# Sheet1.net
KiCad netlist of a schematic drawn in Altium Designer
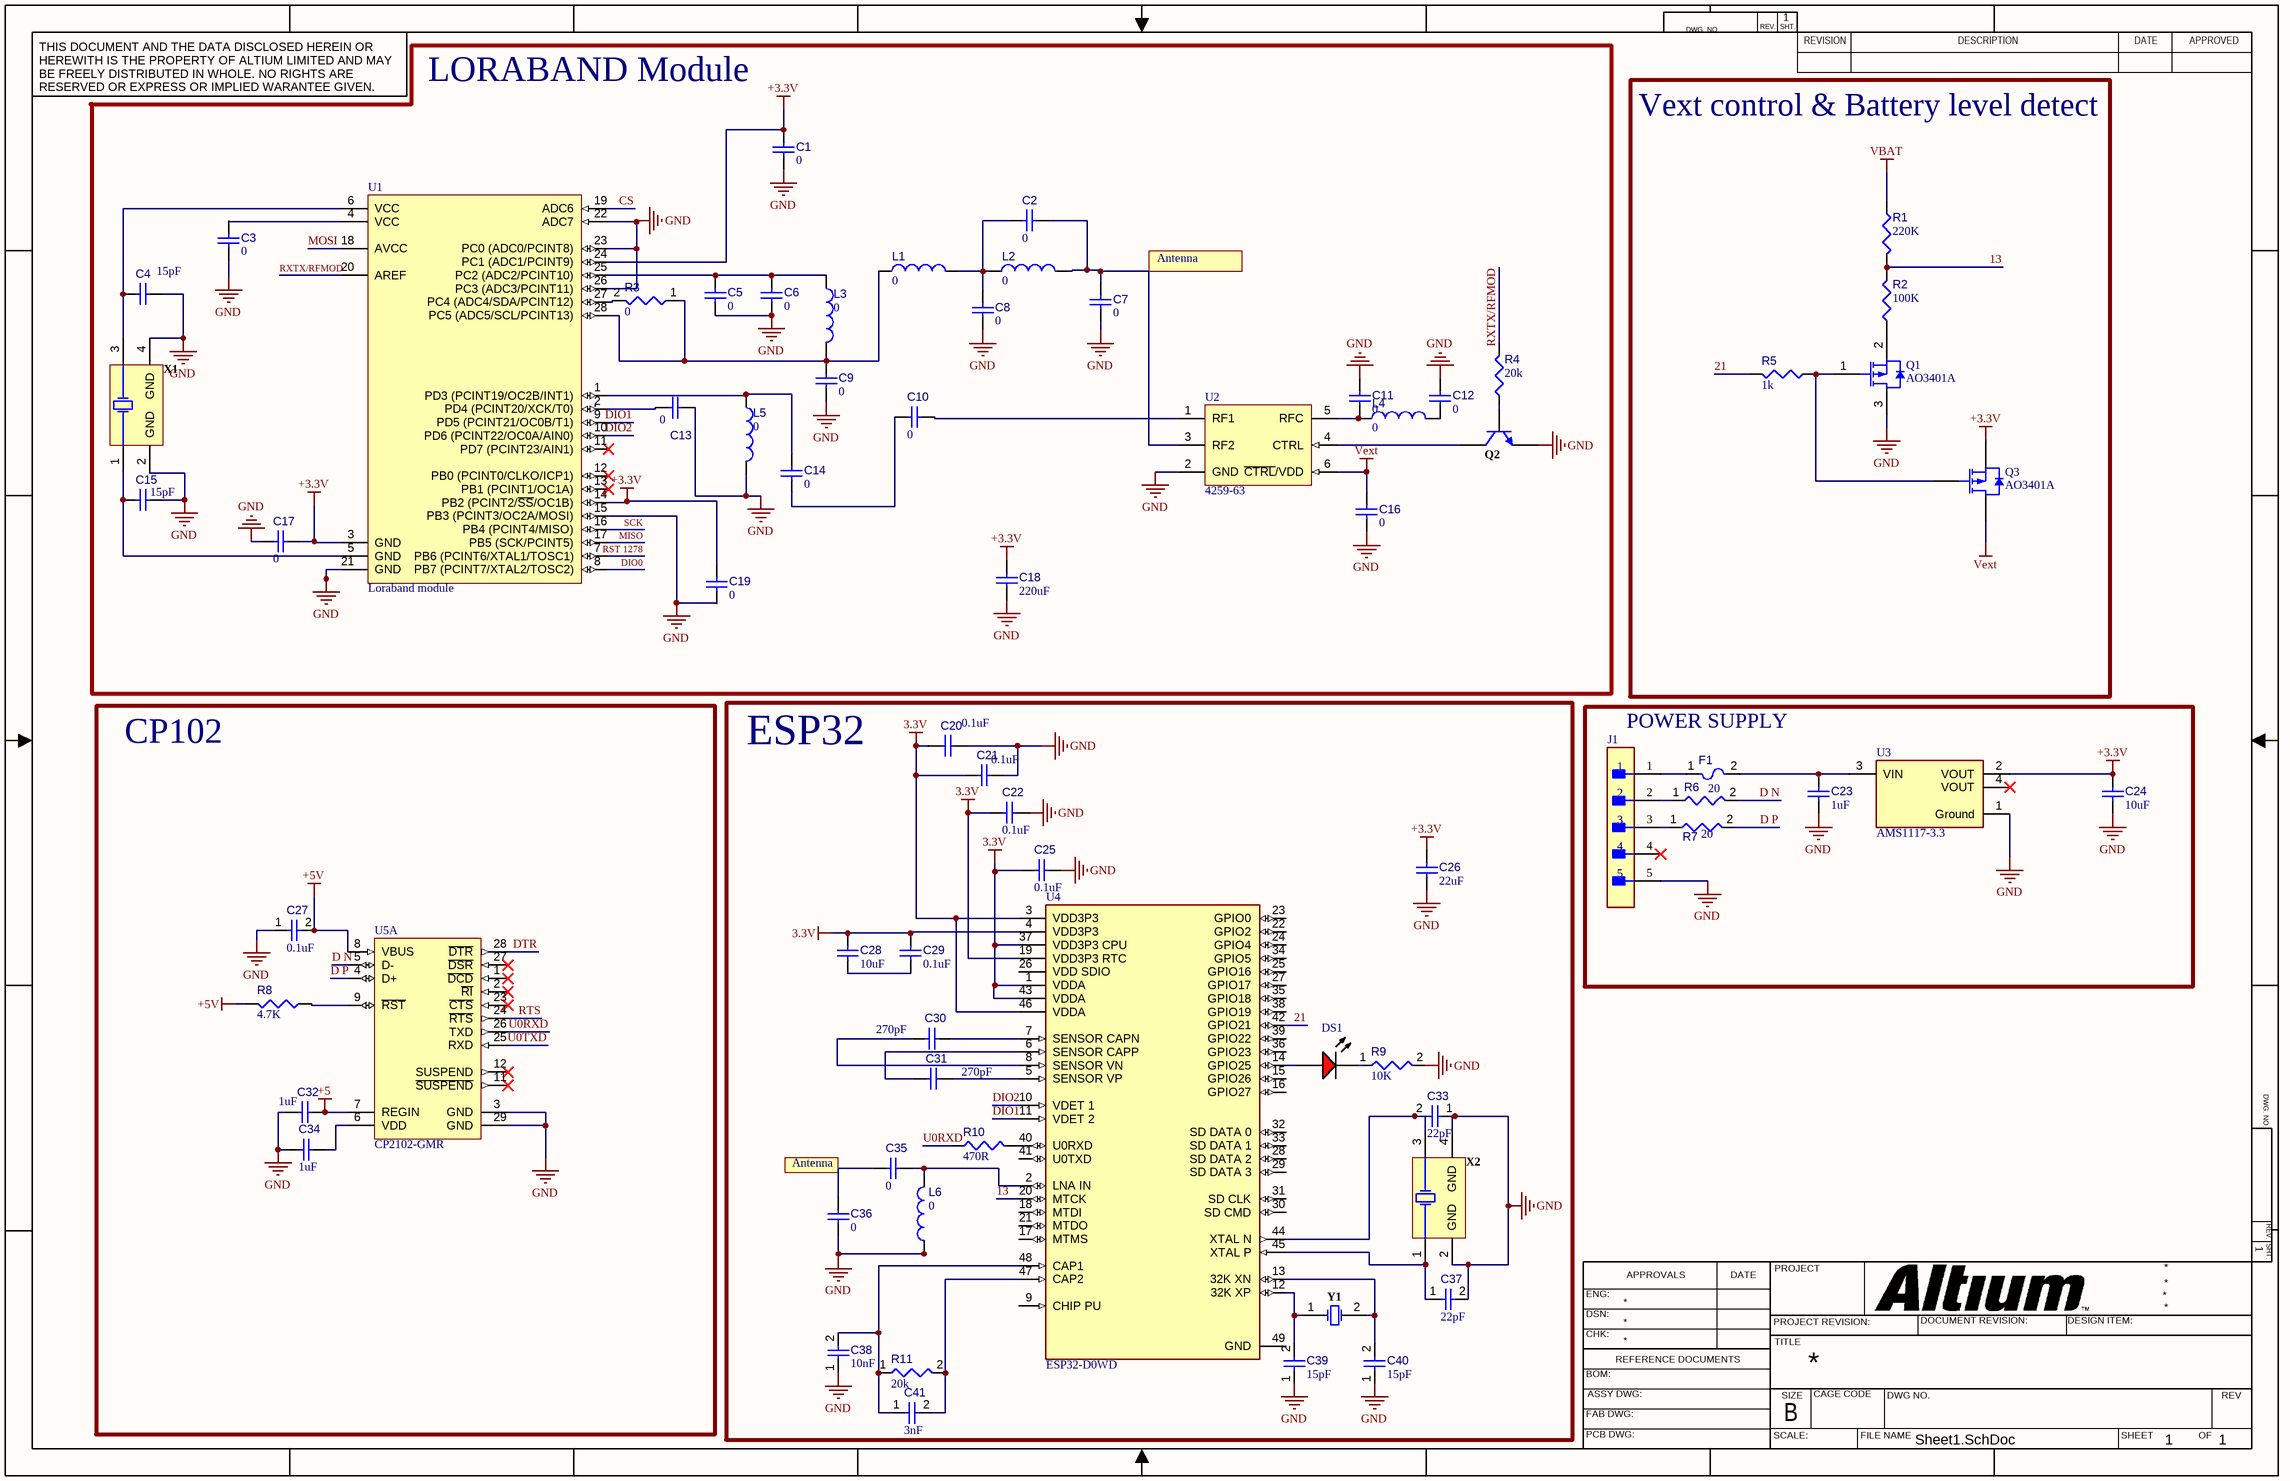
[diagram p0: Sheet1.SchDoc]

(export (version "E")
  (design (tool "Eeschema 10.0.6"))
  (components
    (comp (ref "C1")
      (value "0")
      (footprint "CAPC0402(1005)60_L")
      (description "Chip Capacitor, 10nF +/-20%, 50V, 0402, Thickness 0.6 mm")
      (fields (field (name "TOLERANCE") "5%") (field (name "Comment") "Capacitor 10nF +/-20% 50V 0402"))
      (libsource (lib "University of Moratuwa") (part "CAP-NP-2"))
    )
    (comp (ref "C2")
      (value "0")
      (footprint "CAPC0402(1005)60_L")
      (description "Chip Capacitor, 10nF +/-20%, 50V, 0402, Thickness 0.6 mm")
      (fields (field (name "TOLERANCE") "5%") (field (name "Comment") "Capacitor 10nF +/-20% 50V 0402"))
      (libsource (lib "University of Moratuwa") (part "CAP-NP-2"))
    )
    (comp (ref "C3")
      (value "0")
      (footprint "CAPC0402(1005)60_L")
      (description "Chip Capacitor, 10nF +/-20%, 50V, 0402, Thickness 0.6 mm")
      (fields (field (name "TOLERANCE") "5%") (field (name "Comment") "Capacitor 10nF +/-20% 50V 0402"))
      (libsource (lib "University of Moratuwa") (part "CAP-NP-2"))
    )
    (comp (ref "C4")
      (value "15pF")
      (footprint "CAPC0402(1005)60_L")
      (description "Chip Capacitor, 10nF +/-20%, 50V, 0402, Thickness 0.6 mm")
      (fields (field (name "TOLERANCE") "5%") (field (name "Comment") "Capacitor 10nF +/-20% 50V 0402"))
      (libsource (lib "University of Moratuwa") (part "CAP-NP-2"))
    )
    (comp (ref "C5")
      (value "0")
      (footprint "CAPC0402(1005)60_L")
      (description "Chip Capacitor, 10nF +/-20%, 50V, 0402, Thickness 0.6 mm")
      (fields (field (name "TOLERANCE") "5%") (field (name "Comment") "Capacitor 10nF +/-20% 50V 0402"))
      (libsource (lib "University of Moratuwa") (part "CAP-NP-2"))
    )
    (comp (ref "C6")
      (value "0")
      (footprint "CAPC0402(1005)60_L")
      (description "Chip Capacitor, 10nF +/-20%, 50V, 0402, Thickness 0.6 mm")
      (fields (field (name "TOLERANCE") "5%") (field (name "Comment") "Capacitor 10nF +/-20% 50V 0402"))
      (libsource (lib "University of Moratuwa") (part "CAP-NP-2"))
    )
    (comp (ref "C7")
      (value "0")
      (footprint "CAPC0402(1005)60_L")
      (description "Chip Capacitor, 10nF +/-20%, 50V, 0402, Thickness 0.6 mm")
      (fields (field (name "TOLERANCE") "5%") (field (name "Comment") "Capacitor 10nF +/-20% 50V 0402"))
      (libsource (lib "University of Moratuwa") (part "CAP-NP-2"))
    )
    (comp (ref "C8")
      (value "0")
      (footprint "CAPC0402(1005)60_L")
      (description "Chip Capacitor, 10nF +/-20%, 50V, 0402, Thickness 0.6 mm")
      (fields (field (name "TOLERANCE") "5%") (field (name "Comment") "Capacitor 10nF +/-20% 50V 0402"))
      (libsource (lib "University of Moratuwa") (part "CAP-NP-2"))
    )
    (comp (ref "C9")
      (value "0")
      (footprint "CAPC0402(1005)60_L")
      (description "Chip Capacitor, 10nF +/-20%, 50V, 0402, Thickness 0.6 mm")
      (fields (field (name "TOLERANCE") "5%") (field (name "Comment") "Capacitor 10nF +/-20% 50V 0402"))
      (libsource (lib "University of Moratuwa") (part "CAP-NP-2"))
    )
    (comp (ref "C10")
      (value "0")
      (footprint "CAPC0402(1005)60_L")
      (description "Chip Capacitor, 10nF +/-20%, 50V, 0402, Thickness 0.6 mm")
      (fields (field (name "TOLERANCE") "5%") (field (name "Comment") "Capacitor 10nF +/-20% 50V 0402"))
      (libsource (lib "University of Moratuwa") (part "CAP-NP-2"))
    )
    (comp (ref "C11")
      (value "0")
      (footprint "CAPC0402(1005)60_L")
      (description "Chip Capacitor, 10nF +/-20%, 50V, 0402, Thickness 0.6 mm")
      (fields (field (name "TOLERANCE") "5%") (field (name "Comment") "Capacitor 10nF +/-20% 50V 0402"))
      (libsource (lib "University of Moratuwa") (part "CAP-NP-2"))
    )
    (comp (ref "C12")
      (value "0")
      (footprint "CAPC0402(1005)60_L")
      (description "Chip Capacitor, 10nF +/-20%, 50V, 0402, Thickness 0.6 mm")
      (fields (field (name "TOLERANCE") "5%") (field (name "Comment") "Capacitor 10nF +/-20% 50V 0402"))
      (libsource (lib "University of Moratuwa") (part "CAP-NP-2"))
    )
    (comp (ref "C13")
      (value "0")
      (footprint "CAPC0402(1005)60_L")
      (description "Chip Capacitor, 10nF +/-20%, 50V, 0402, Thickness 0.6 mm")
      (fields (field (name "TOLERANCE") "5%") (field (name "Comment") "Capacitor 10nF +/-20% 50V 0402"))
      (libsource (lib "University of Moratuwa") (part "CAP-NP-2"))
    )
    (comp (ref "C14")
      (value "0")
      (footprint "CAPC0402(1005)60_L")
      (description "Chip Capacitor, 10nF +/-20%, 50V, 0402, Thickness 0.6 mm")
      (fields (field (name "TOLERANCE") "5%") (field (name "Comment") "Capacitor 10nF +/-20% 50V 0402"))
      (libsource (lib "University of Moratuwa") (part "CAP-NP-2"))
    )
    (comp (ref "C15")
      (value "15pF")
      (footprint "CAPC0402(1005)60_L")
      (description "Chip Capacitor, 10nF +/-20%, 50V, 0402, Thickness 0.6 mm")
      (fields (field (name "TOLERANCE") "5%") (field (name "Comment") "Capacitor 10nF +/-20% 50V 0402"))
      (libsource (lib "University of Moratuwa") (part "CAP-NP-2"))
    )
    (comp (ref "C16")
      (value "0")
      (footprint "CAPC0402(1005)60_L")
      (description "Chip Capacitor, 10nF +/-20%, 50V, 0402, Thickness 0.6 mm")
      (fields (field (name "TOLERANCE") "5%") (field (name "Comment") "Capacitor 10nF +/-20% 50V 0402"))
      (libsource (lib "University of Moratuwa") (part "CAP-NP-2"))
    )
    (comp (ref "C17")
      (value "0")
      (footprint "CAPC0402(1005)60_L")
      (description "Chip Capacitor, 10nF +/-20%, 50V, 0402, Thickness 0.6 mm")
      (fields (field (name "TOLERANCE") "5%") (field (name "Comment") "Capacitor 10nF +/-20% 50V 0402"))
      (libsource (lib "University of Moratuwa") (part "CAP-NP-2"))
    )
    (comp (ref "C18")
      (value "220uF")
      (footprint "CAPC0402(1005)60_L")
      (description "Chip Capacitor, 10nF +/-20%, 50V, 0402, Thickness 0.6 mm")
      (fields (field (name "TOLERANCE") "5%") (field (name "Comment") "Capacitor 10nF +/-20% 50V 0402"))
      (libsource (lib "University of Moratuwa") (part "CAP-NP-2"))
    )
    (comp (ref "C19")
      (value "0")
      (footprint "CAPC0402(1005)60_L")
      (description "Chip Capacitor, 10nF +/-20%, 50V, 0402, Thickness 0.6 mm")
      (fields (field (name "TOLERANCE") "5%") (field (name "Comment") "Capacitor 10nF +/-20% 50V 0402"))
      (libsource (lib "University of Moratuwa") (part "CAP-NP-2"))
    )
    (comp (ref "C20")
      (value "0.1uF")
      (footprint "CAPC0402(1005)60_L")
      (description "Chip Capacitor, 10nF +/-20%, 50V, 0402, Thickness 0.6 mm")
      (fields (field (name "TOLERANCE") "5%") (field (name "Comment") "Capacitor 10nF +/-20% 50V 0402"))
      (libsource (lib "University of Moratuwa") (part "CAP-NP-2"))
    )
    (comp (ref "C21")
      (value "0.1uF")
      (footprint "CAPC0402(1005)60_L")
      (description "Chip Capacitor, 10nF +/-20%, 50V, 0402, Thickness 0.6 mm")
      (fields (field (name "TOLERANCE") "5%") (field (name "Comment") "Capacitor 10nF +/-20% 50V 0402"))
      (libsource (lib "University of Moratuwa") (part "CAP-NP-2"))
    )
    (comp (ref "C22")
      (value "0.1uF")
      (footprint "CAPC0402(1005)60_L")
      (description "Chip Capacitor, 10nF +/-20%, 50V, 0402, Thickness 0.6 mm")
      (fields (field (name "TOLERANCE") "5%") (field (name "Comment") "Capacitor 10nF +/-20% 50V 0402"))
      (libsource (lib "University of Moratuwa") (part "CAP-NP-2"))
    )
    (comp (ref "C23")
      (value "1uF")
      (footprint "CAPC0402(1005)60_L")
      (description "Chip Capacitor, 10nF +/-20%, 50V, 0402, Thickness 0.6 mm")
      (fields (field (name "TOLERANCE") "5%") (field (name "Comment") "Capacitor 10nF +/-20% 50V 0402"))
      (libsource (lib "University of Moratuwa") (part "CAP-NP-2"))
    )
    (comp (ref "C24")
      (value "10uF")
      (footprint "CAPC0402(1005)60_L")
      (description "Chip Capacitor, 10nF +/-20%, 50V, 0402, Thickness 0.6 mm")
      (fields (field (name "TOLERANCE") "5%") (field (name "Comment") "Capacitor 10nF +/-20% 50V 0402"))
      (libsource (lib "University of Moratuwa") (part "CAP-NP-2"))
    )
    (comp (ref "C25")
      (value "0.1uF")
      (footprint "CAPC0402(1005)60_L")
      (description "Chip Capacitor, 10nF +/-20%, 50V, 0402, Thickness 0.6 mm")
      (fields (field (name "TOLERANCE") "5%") (field (name "Comment") "Capacitor 10nF +/-20% 50V 0402"))
      (libsource (lib "University of Moratuwa") (part "CAP-NP-2"))
    )
    (comp (ref "C26")
      (value "22uF")
      (footprint "CAPC0402(1005)60_L")
      (description "Chip Capacitor, 10nF +/-20%, 50V, 0402, Thickness 0.6 mm")
      (fields (field (name "TOLERANCE") "5%") (field (name "Comment") "Capacitor 10nF +/-20% 50V 0402"))
      (libsource (lib "University of Moratuwa") (part "CAP-NP-2"))
    )
    (comp (ref "C27")
      (value "0.1uF")
      (footprint "CAPC0402(1005)60_L")
      (description "Chip Capacitor, 10nF +/-20%, 50V, 0402, Thickness 0.6 mm")
      (fields (field (name "TOLERANCE") "5%") (field (name "Comment") "Capacitor 10nF +/-20% 50V 0402"))
      (libsource (lib "") (part "CAP-NP-2_1"))
    )
    (comp (ref "C28")
      (value "10uF")
      (footprint "CAPC0402(1005)60_L")
      (description "Chip Capacitor, 10nF +/-20%, 50V, 0402, Thickness 0.6 mm")
      (fields (field (name "TOLERANCE") "5%") (field (name "Comment") "Capacitor 10nF +/-20% 50V 0402"))
      (libsource (lib "University of Moratuwa") (part "CAP-NP-2"))
    )
    (comp (ref "C29")
      (value "0.1uF")
      (footprint "CAPC0402(1005)60_L")
      (description "Chip Capacitor, 10nF +/-20%, 50V, 0402, Thickness 0.6 mm")
      (fields (field (name "TOLERANCE") "5%") (field (name "Comment") "Capacitor 10nF +/-20% 50V 0402"))
      (libsource (lib "University of Moratuwa") (part "CAP-NP-2"))
    )
    (comp (ref "C30")
      (value "270pF")
      (footprint "CAPC0402(1005)60_L")
      (description "Chip Capacitor, 10nF +/-20%, 50V, 0402, Thickness 0.6 mm")
      (fields (field (name "TOLERANCE") "5%") (field (name "Comment") "Capacitor 10nF +/-20% 50V 0402"))
      (libsource (lib "University of Moratuwa") (part "CAP-NP-2"))
    )
    (comp (ref "C31")
      (value "270pF")
      (footprint "CAPC0402(1005)60_L")
      (description "Chip Capacitor, 10nF +/-20%, 50V, 0402, Thickness 0.6 mm")
      (fields (field (name "TOLERANCE") "5%") (field (name "Comment") "Capacitor 10nF +/-20% 50V 0402"))
      (libsource (lib "University of Moratuwa") (part "CAP-NP-2"))
    )
    (comp (ref "C32")
      (value "1uF")
      (footprint "CAPC0402(1005)60_L")
      (description "Chip Capacitor, 10nF +/-20%, 50V, 0402, Thickness 0.6 mm")
      (fields (field (name "TOLERANCE") "5%") (field (name "Comment") "Capacitor 10nF +/-20% 50V 0402"))
      (libsource (lib "University of Moratuwa") (part "CAP-NP-2"))
    )
    (comp (ref "C33")
      (value "22pF")
      (footprint "CAPC0402(1005)60_L")
      (description "Chip Capacitor, 10nF +/-20%, 50V, 0402, Thickness 0.6 mm")
      (fields (field (name "TOLERANCE") "5%") (field (name "Comment") "Capacitor 10nF +/-20% 50V 0402"))
      (libsource (lib "") (part "CAP-NP-2_1"))
    )
    (comp (ref "C34")
      (value "1uF")
      (footprint "CAPC0402(1005)60_L")
      (description "Chip Capacitor, 10nF +/-20%, 50V, 0402, Thickness 0.6 mm")
      (fields (field (name "TOLERANCE") "5%") (field (name "Comment") "Capacitor 10nF +/-20% 50V 0402"))
      (libsource (lib "University of Moratuwa") (part "CAP-NP-2"))
    )
    (comp (ref "C35")
      (value "0")
      (footprint "CAPC0402(1005)60_L")
      (description "Chip Capacitor, 10nF +/-20%, 50V, 0402, Thickness 0.6 mm")
      (fields (field (name "TOLERANCE") "5%") (field (name "Comment") "Capacitor 10nF +/-20% 50V 0402"))
      (libsource (lib "University of Moratuwa") (part "CAP-NP-2"))
    )
    (comp (ref "C36")
      (value "0")
      (footprint "CAPC0402(1005)60_L")
      (description "Chip Capacitor, 10nF +/-20%, 50V, 0402, Thickness 0.6 mm")
      (fields (field (name "TOLERANCE") "5%") (field (name "Comment") "Capacitor 10nF +/-20% 50V 0402"))
      (libsource (lib "University of Moratuwa") (part "CAP-NP-2"))
    )
    (comp (ref "C37")
      (value "22pF")
      (footprint "CAPC0402(1005)60_L")
      (description "Chip Capacitor, 10nF +/-20%, 50V, 0402, Thickness 0.6 mm")
      (fields (field (name "TOLERANCE") "5%") (field (name "Comment") "Capacitor 10nF +/-20% 50V 0402"))
      (libsource (lib "") (part "CAP-NP-2_1"))
    )
    (comp (ref "C38")
      (value "10nF")
      (footprint "CAPC0402(1005)60_L")
      (description "Chip Capacitor, 10nF +/-20%, 50V, 0402, Thickness 0.6 mm")
      (fields (field (name "TOLERANCE") "5%") (field (name "Comment") "Capacitor 10nF +/-20% 50V 0402"))
      (libsource (lib "") (part "CAP-NP-2_1"))
    )
    (comp (ref "C39")
      (value "15pF")
      (footprint "CAPC0402(1005)60_L")
      (description "Chip Capacitor, 10nF +/-20%, 50V, 0402, Thickness 0.6 mm")
      (fields (field (name "TOLERANCE") "5%") (field (name "Comment") "Capacitor 10nF +/-20% 50V 0402"))
      (libsource (lib "") (part "CAP-NP-2_1"))
    )
    (comp (ref "C40")
      (value "15pF")
      (footprint "CAPC0402(1005)60_L")
      (description "Chip Capacitor, 10nF +/-20%, 50V, 0402, Thickness 0.6 mm")
      (fields (field (name "TOLERANCE") "5%") (field (name "Comment") "Capacitor 10nF +/-20% 50V 0402"))
      (libsource (lib "") (part "CAP-NP-2_1"))
    )
    (comp (ref "C41")
      (value "3nF")
      (footprint "CAPC0402(1005)60_L")
      (description "Chip Capacitor, 10nF +/-20%, 50V, 0402, Thickness 0.6 mm")
      (fields (field (name "TOLERANCE") "5%") (field (name "Comment") "Capacitor 10nF +/-20% 50V 0402"))
      (libsource (lib "") (part "CAP-NP-2_1"))
    )
    (comp (ref "DS1")
      (value "TLMS1100-GS08")
      (footprint "VISH-TLMX1100_V")
      (description "Red Led, 20mA, 2.1 V, -40 to 100 degC, 2-Pin SMD (0603), RoHS, Tape and Reel")
      (fields (field (name "MANUFACTURER") "Vishay Semiconductor") (field (name "POWER") "90mW"))
      (libsource (lib "University of Moratuwa") (part "LED-RED-AK-2"))
    )
    (comp (ref "F1")
      (value "MF-MSMF050")
      (footprint "BOUR-MF-MSMF050-2_V")
      (description "PTC Resettable Fuse, 15 V, 500 mA, -40 to 85 degC, 2-Pin SMD, RoHS, Tape and Reel")
      (fields (field (name "MANUFACTURER") "Bourns"))
      (libsource (lib "University of Moratuwa") (part "FUSE-2"))
    )
    (comp (ref "J1")
      (value "22-28-4050")
      (footprint "FP-22-28-4050-MFG")
      (libsource (lib "Altium Content Vault") (part "bf93c07fd2649a848d0ec8585582aab"))
    )
    (comp (ref "L1")
      (value "0")
      (footprint "SUSUMU-PCMB063T_V")
      (description "Shielded Wirewound Inductor, 2.2 uH, +/- 20%, -20 to 120 degC, 2-Pin SMD, RoHS, Tape and Reel")
      (fields (field (name "TOLERANCE") "20%") (field (name "Comment") "PCMB063T-2R2MS"))
      (libsource (lib "University of Moratuwa") (part "CMP-001-0020-1"))
    )
    (comp (ref "L2")
      (value "0")
      (footprint "SUSUMU-PCMB063T_V")
      (description "Shielded Wirewound Inductor, 2.2 uH, +/- 20%, -20 to 120 degC, 2-Pin SMD, RoHS, Tape and Reel")
      (fields (field (name "TOLERANCE") "20%") (field (name "Comment") "PCMB063T-2R2MS"))
      (libsource (lib "University of Moratuwa") (part "CMP-001-0020-1"))
    )
    (comp (ref "L3")
      (value "0")
      (footprint "SUSUMU-PCMB063T_V")
      (description "Shielded Wirewound Inductor, 2.2 uH, +/- 20%, -20 to 120 degC, 2-Pin SMD, RoHS, Tape and Reel")
      (fields (field (name "TOLERANCE") "20%") (field (name "Comment") "PCMB063T-2R2MS"))
      (libsource (lib "University of Moratuwa") (part "CMP-001-0020-1"))
    )
    (comp (ref "L4")
      (value "0")
      (footprint "SUSUMU-PCMB063T_V")
      (description "Shielded Wirewound Inductor, 2.2 uH, +/- 20%, -20 to 120 degC, 2-Pin SMD, RoHS, Tape and Reel")
      (fields (field (name "TOLERANCE") "20%") (field (name "Comment") "PCMB063T-2R2MS"))
      (libsource (lib "University of Moratuwa") (part "CMP-001-0020-1"))
    )
    (comp (ref "L5")
      (value "0")
      (footprint "SUSUMU-PCMB063T_V")
      (description "Shielded Wirewound Inductor, 2.2 uH, +/- 20%, -20 to 120 degC, 2-Pin SMD, RoHS, Tape and Reel")
      (fields (field (name "TOLERANCE") "20%") (field (name "Comment") "PCMB063T-2R2MS"))
      (libsource (lib "University of Moratuwa") (part "CMP-001-0020-1"))
    )
    (comp (ref "L6")
      (value "0")
      (footprint "SUSUMU-PCMB063T_V")
      (description "Shielded Wirewound Inductor, 2.2 uH, +/- 20%, -20 to 120 degC, 2-Pin SMD, RoHS, Tape and Reel")
      (fields (field (name "TOLERANCE") "20%") (field (name "Comment") "PCMB063T-2R2MS"))
      (libsource (lib "University of Moratuwa") (part "CMP-001-0020-1"))
    )
    (comp (ref "Q1")
      (value "AO3401A")
      (footprint "AO-SOT-23-3L_V")
      (description "P-Channel MOSFET, 30 V, 4 A, -55 to 150 degC, 3-Pin SOT-23-3L, RoHS, Tape and Reel")
      (fields (field (name "MANUFACTURER") "Alpha and Omega"))
      (libsource (lib "") (part "PEMOS-GSD-3_1"))
    )
    (comp (ref "Q2")
      (value "2SC3356-T1B-A")
      (footprint "RENE-2SC3356-A-3_N")
      (fields (field (name "MANUFACTURER") "Renesas"))
      (libsource (lib "Altium Content Vault") (part "RENE-E1B2C3-NPN-3"))
    )
    (comp (ref "Q3")
      (value "AO3401A")
      (footprint "AO-SOT-23-3L_V")
      (description "P-Channel MOSFET, 30 V, 4 A, -55 to 150 degC, 3-Pin SOT-23-3L, RoHS, Tape and Reel")
      (fields (field (name "MANUFACTURER") "Alpha and Omega"))
      (libsource (lib "Altium Content Vault") (part "PEMOS-GSD-3"))
    )
    (comp (ref "R1")
      (value "220K")
      (footprint "RESC1609X50X30ML08T20")
      (description "Chip Resistor, 22 Ohm, +/- 1%, 100 mW, -55 to 155 degC, 0603 (1608 Metric)")
      (fields (field (name "POWER") "100mW") (field (name "TOLERANCE") "1%"))
      (libsource (lib "University of Moratuwa") (part "RES-2"))
    )
    (comp (ref "R2")
      (value "100K")
      (footprint "RESC1609X50X30ML08T20")
      (description "Chip Resistor, 22 Ohm, +/- 1%, 100 mW, -55 to 155 degC, 0603 (1608 Metric)")
      (fields (field (name "POWER") "100mW") (field (name "TOLERANCE") "1%"))
      (libsource (lib "University of Moratuwa") (part "RES-2"))
    )
    (comp (ref "R3")
      (value "0")
      (footprint "RESC1609X50X30ML08T20")
      (description "Chip Resistor, 22 Ohm, +/- 1%, 100 mW, -55 to 155 degC, 0603 (1608 Metric)")
      (fields (field (name "POWER") "100mW") (field (name "TOLERANCE") "1%"))
      (libsource (lib "") (part "RES-2_1"))
    )
    (comp (ref "R4")
      (value "20k")
      (footprint "RESC1609X50X30ML08T20")
      (description "Chip Resistor, 22 Ohm, +/- 1%, 100 mW, -55 to 155 degC, 0603 (1608 Metric)")
      (fields (field (name "POWER") "100mW") (field (name "TOLERANCE") "1%"))
      (libsource (lib "University of Moratuwa") (part "RES-2"))
    )
    (comp (ref "R5")
      (value "1k")
      (footprint "RESC1609X50X30ML08T20")
      (description "Chip Resistor, 22 Ohm, +/- 1%, 100 mW, -55 to 155 degC, 0603 (1608 Metric)")
      (fields (field (name "POWER") "100mW") (field (name "TOLERANCE") "1%"))
      (libsource (lib "University of Moratuwa") (part "RES-2"))
    )
    (comp (ref "R6")
      (value "20")
      (footprint "RESC1609X50X30ML08T20")
      (description "Chip Resistor, 22 Ohm, +/- 1%, 100 mW, -55 to 155 degC, 0603 (1608 Metric)")
      (fields (field (name "POWER") "100mW") (field (name "TOLERANCE") "1%"))
      (libsource (lib "") (part "RES-2_1"))
    )
    (comp (ref "R7")
      (value "20")
      (footprint "RESC1609X50X30ML08T20")
      (description "Chip Resistor, 22 Ohm, +/- 1%, 100 mW, -55 to 155 degC, 0603 (1608 Metric)")
      (fields (field (name "POWER") "100mW") (field (name "TOLERANCE") "1%"))
      (libsource (lib "") (part "RES-2_1"))
    )
    (comp (ref "R8")
      (value "4.7K")
      (footprint "RESC1609X50X30ML08T20")
      (description "Chip Resistor, 22 Ohm, +/- 1%, 100 mW, -55 to 155 degC, 0603 (1608 Metric)")
      (fields (field (name "POWER") "100mW") (field (name "TOLERANCE") "1%"))
      (libsource (lib "University of Moratuwa") (part "RES-2"))
    )
    (comp (ref "R9")
      (value "10K")
      (footprint "RESC1609X50X30ML08T20")
      (description "Chip Resistor, 22 Ohm, +/- 1%, 100 mW, -55 to 155 degC, 0603 (1608 Metric)")
      (fields (field (name "POWER") "100mW") (field (name "TOLERANCE") "1%"))
      (libsource (lib "") (part "RES-2_1"))
    )
    (comp (ref "R10")
      (value "470R")
      (footprint "RESC1609X50X30ML08T20")
      (description "Chip Resistor, 22 Ohm, +/- 1%, 100 mW, -55 to 155 degC, 0603 (1608 Metric)")
      (fields (field (name "POWER") "100mW") (field (name "TOLERANCE") "1%"))
      (libsource (lib "University of Moratuwa") (part "RES-2"))
    )
    (comp (ref "R11")
      (value "20k")
      (footprint "RESC1609X50X30ML08T20")
      (description "Chip Resistor, 22 Ohm, +/- 1%, 100 mW, -55 to 155 degC, 0603 (1608 Metric)")
      (fields (field (name "POWER") "100mW") (field (name "TOLERANCE") "1%"))
      (libsource (lib "") (part "RES-2_1"))
    )
    (comp (ref "U1")
      (value "Loraband module")
      (footprint "32A_L")
      (libsource (lib "Altium Content Vault") (part "MC-8B-ATM48-SQ32"))
    )
    (comp (ref "U2")
      (value "4259-63")
      (footprint "PERE-SC-70-6_M")
      (description "IC RF Switch SPDT, 50 Ohm, 6-Pin SC70, RoHS, Tape and Reel")
      (fields (field (name "MANUFACTURER") "Peregrine Semiconductor"))
      (libsource (lib "Altium Content Vault") (part "PERE-PE4259-6"))
    )
    (comp (ref "U3")
      (value "AMS1117-3.3")
      (footprint "FP-AMS1117-IPC_C")
      (description "LDO Voltage Regulators 1A, 3.3V")
      (fields
        (field (name "OCTOPART") "https://octopart.com/ams1117-3.3-advanced+monolithic+systems-25899300")
        (field (name "MANUFACTURER") "Advanced Monolithic Systems")
      )
      (libsource (lib "Altium Content Vault") (part "8bdbb5f8e77002000e30dd2845d0354"))
    )
    (comp (ref "U4")
      (value "ESP32-D0WD")
      (footprint "FP-ESP32-D0WD-IPC_C")
      (description "IC RF TXRX+MCU BLUETOOTH 48VFQFN")
      (fields
        (field (name "MANUFACTURER") "Espressif")
        (field (name "OCTOPART") "https://octopart.com/esp32-d0wd-espressif+systems-89169964")
      )
      (libsource (lib "Altium Content Vault") (part "c80bf60791df05506f5971a813c8896"))
    )
    (comp (ref "U5")
      (value "CP2102-GMR")
      (footprint "SLAB-QFN-28-3125x3125TP_M")
      (description "Single-Chip USB to URAT Bridge, 3.3 V, -40 to 85 degC, 28-Pin QFN, RoHS, Tape and Reel")
      (fields (field (name "MANUFACTURER") "Silicon Labs"))
      (libsource (lib "Altium Content Vault") (part "SLAB-CP210X-QFN-28-29"))
    )
    (comp (ref "X1")
      (value "7B-24.000MAAJ-T")
      (footprint "TXC-7B-4_V")
      (fields (field (name "TOLERANCE") "30ppm") (field (name "MANUFACTURER") "TXC"))
      (libsource (lib "University of Moratuwa") (part "XTAL-1-3-4"))
    )
    (comp (ref "X2")
      (value "7B-40.000MAAJ-T")
      (footprint "TXC-7B-4_V")
      (description "9B Series Quartz Crystal, 40 MHz, +/-30 ppm, 18 pF, -40 to 85 degC, 4-Pin SMD, RoHS, Tape and Reel")
      (fields (field (name "TOLERANCE") "30ppm") (field (name "MANUFACTURER") "TXC"))
      (libsource (lib "University of Moratuwa") (part "XTAL-1-3-4"))
    )
    (comp (ref "Y1")
      (value "9HT10-32.768KDZF-T")
      (footprint "TXC-9HT10_V")
      (description "Tuning Fork, 32.768 KHz, +/-20 ppm, 12.5 pF, -40 to 85 degC, 2-Pin SMD, RoHS, Tape and Reel")
      (fields (field (name "TOLERANCE") "20ppm") (field (name "MANUFACTURER") "TXC"))
      (libsource (lib "University of Moratuwa") (part "XTAL-1-2-2"))
    )
  )
  (nets
    (net (code "1") (name "+3.3V") (class "Default")
      (node (ref "C1") (pin "1") (pinfunction "1_1") (pintype "passive"))
      (node (ref "C17") (pin "1") (pinfunction "1_1") (pintype "passive"))
      (node (ref "C18") (pin "2") (pinfunction "2_2") (pintype "passive"))
      (node (ref "C19") (pin "2") (pinfunction "2_2") (pintype "passive"))
      (node (ref "C24") (pin "1") (pinfunction "1_1") (pintype "passive"))
      (node (ref "C26") (pin "2") (pinfunction "2_2") (pintype "passive"))
      (node (ref "Q3") (pin "2") (pinfunction "SOURCE_2") (pintype "passive"))
      (node (ref "U1") (pin "14") (pinfunction "PB2_(PCINT2/~{SS}/OC1B)_14") (pintype "bidirectional"))
      (node (ref "U1") (pin "24") (pinfunction "PC1_(ADC1/PCINT9)_24") (pintype "bidirectional"))
      (node (ref "U1") (pin "3") (pinfunction "GND_3") (pintype "power_in"))
      (node (ref "U3") (pin "2") (pinfunction "VOUT_2") (pintype "passive"))
    )
    (net (code "2") (name "+5") (class "Default")
      (node (ref "C32") (pin "2") (pinfunction "2_2") (pintype "passive"))
      (node (ref "U5") (pin "7") (pinfunction "REGIN_7") (pintype "power_in"))
    )
    (net (code "3") (name "+5V") (class "Default")
      (node (ref "C27") (pin "2") (pinfunction "2_2") (pintype "passive"))
      (node (ref "R8") (pin "2") (pinfunction "2_2") (pintype "passive"))
      (node (ref "U5") (pin "8") (pinfunction "VBUS_8") (pintype "input"))
    )
    (net (code "4") (name "/13") (class "Default")
      (node (ref "R1") (pin "2") (pinfunction "2_2") (pintype "passive"))
      (node (ref "R2") (pin "2") (pinfunction "2_2") (pintype "passive"))
      (node (ref "U4") (pin "20") (pinfunction "MTCK_20") (pintype "bidirectional"))
    )
    (net (code "5") (name "/21") (class "Default")
      (node (ref "R5") (pin "2") (pinfunction "2_2") (pintype "passive"))
      (node (ref "U4") (pin "42") (pinfunction "GPIO21_42") (pintype "bidirectional"))
    )
    (net (code "6") (name "/CS") (class "Default")
      (node (ref "U1") (pin "19") (pinfunction "ADC6_19") (pintype "input"))
    )
    (net (code "7") (name "/D N") (class "Default")
      (node (ref "R6") (pin "2") (pinfunction "2_2") (pintype "passive"))
      (node (ref "U5") (pin "5") (pinfunction "D-_5") (pintype "bidirectional"))
    )
    (net (code "8") (name "/D P") (class "Default")
      (node (ref "R7") (pin "2") (pinfunction "2_2") (pintype "passive"))
      (node (ref "U5") (pin "4") (pinfunction "D+_4") (pintype "bidirectional"))
    )
    (net (code "9") (name "/DIO0") (class "Default")
      (node (ref "U1") (pin "8") (pinfunction "PB7_(PCINT7/XTAL2/TOSC2)_8") (pintype "bidirectional"))
    )
    (net (code "10") (name "/DIO1") (class "Default")
      (node (ref "U1") (pin "9") (pinfunction "PD5_(PCINT21/OC0B/T1)_9") (pintype "bidirectional"))
      (node (ref "U4") (pin "11") (pinfunction "VDET_2_11") (pintype "input"))
    )
    (net (code "11") (name "/DIO2") (class "Default")
      (node (ref "U1") (pin "10") (pinfunction "PD6_(PCINT22/OC0A/AIN0)_10") (pintype "bidirectional"))
      (node (ref "U4") (pin "10") (pinfunction "VDET_1_10") (pintype "input"))
    )
    (net (code "12") (name "/DTR") (class "Default")
      (node (ref "U5") (pin "28") (pinfunction "~{DTR}_28") (pintype "output"))
    )
    (net (code "13") (name "/MISO") (class "Default")
      (node (ref "U1") (pin "17") (pinfunction "PB5_(SCK/PCINT5)_17") (pintype "bidirectional"))
    )
    (net (code "14") (name "/MOSI") (class "Default")
      (node (ref "U1") (pin "18") (pinfunction "AVCC_18") (pintype "power_in"))
    )
    (net (code "15") (name "/RST 1278") (class "Default")
      (node (ref "U1") (pin "7") (pinfunction "PB6_(PCINT6/XTAL1/TOSC1)_7") (pintype "bidirectional"))
    )
    (net (code "16") (name "/RTS") (class "Default")
      (node (ref "U5") (pin "24") (pinfunction "~{RTS}_24") (pintype "output"))
    )
    (net (code "17") (name "/RXTX{slash}RFMOD") (class "Default")
      (node (ref "R4") (pin "2") (pinfunction "2_2") (pintype "passive"))
      (node (ref "U1") (pin "20") (pinfunction "AREF_20") (pintype "passive"))
    )
    (net (code "18") (name "/SCK") (class "Default")
      (node (ref "U1") (pin "16") (pinfunction "PB4_(PCINT4/MISO)_16") (pintype "bidirectional"))
    )
    (net (code "19") (name "/U0RXD") (class "Default")
      (node (ref "R10") (pin "1") (pinfunction "1_1") (pintype "passive"))
      (node (ref "U5") (pin "26") (pinfunction "TXD_26") (pintype "output"))
    )
    (net (code "20") (name "/U0TXD") (class "Default")
      (node (ref "U5") (pin "25") (pinfunction "RXD_25") (pintype "input"))
    )
    (net (code "21") (name "3.3V") (class "Default")
      (node (ref "C20") (pin "1") (pinfunction "1_1") (pintype "passive"))
      (node (ref "C21") (pin "1") (pinfunction "1_1") (pintype "passive"))
      (node (ref "C22") (pin "1") (pinfunction "1_1") (pintype "passive"))
      (node (ref "C25") (pin "1") (pinfunction "1_1") (pintype "passive"))
      (node (ref "C28") (pin "1") (pinfunction "1_1") (pintype "passive"))
      (node (ref "C29") (pin "1") (pinfunction "1_1") (pintype "passive"))
      (node (ref "U4") (pin "1") (pinfunction "VDDA_1") (pintype "power_in"))
      (node (ref "U4") (pin "19") (pinfunction "VDD3P3_RTC_19") (pintype "power_in"))
      (node (ref "U4") (pin "3") (pinfunction "VDD3P3_3") (pintype "power_in"))
      (node (ref "U4") (pin "37") (pinfunction "VDD3P3_CPU_37") (pintype "power_in"))
      (node (ref "U4") (pin "4") (pinfunction "VDD3P3_4") (pintype "power_in"))
      (node (ref "U4") (pin "43") (pinfunction "VDDA_43") (pintype "power_in"))
      (node (ref "U4") (pin "46") (pinfunction "VDDA_46") (pintype "power_in"))
    )
    (net (code "22") (name "GND") (class "Default")
      (node (ref "C1") (pin "2") (pinfunction "2_2") (pintype "passive"))
      (node (ref "C11") (pin "1") (pinfunction "1_1") (pintype "passive"))
      (node (ref "C12") (pin "1") (pinfunction "1_1") (pintype "passive"))
      (node (ref "C13") (pin "2") (pinfunction "2_2") (pintype "passive"))
      (node (ref "C15") (pin "2") (pinfunction "2_2") (pintype "passive"))
      (node (ref "C16") (pin "2") (pinfunction "2_2") (pintype "passive"))
      (node (ref "C17") (pin "2") (pinfunction "2_2") (pintype "passive"))
      (node (ref "C18") (pin "1") (pinfunction "1_1") (pintype "passive"))
      (node (ref "C19") (pin "1") (pinfunction "1_1") (pintype "passive"))
      (node (ref "C20") (pin "2") (pinfunction "2_2") (pintype "passive"))
      (node (ref "C21") (pin "2") (pinfunction "2_2") (pintype "passive"))
      (node (ref "C22") (pin "2") (pinfunction "2_2") (pintype "passive"))
      (node (ref "C23") (pin "2") (pinfunction "2_2") (pintype "passive"))
      (node (ref "C24") (pin "2") (pinfunction "2_2") (pintype "passive"))
      (node (ref "C25") (pin "2") (pinfunction "2_2") (pintype "passive"))
      (node (ref "C26") (pin "1") (pinfunction "1_1") (pintype "passive"))
      (node (ref "C27") (pin "1") (pinfunction "1_1") (pintype "passive"))
      (node (ref "C3") (pin "1") (pinfunction "1_1") (pintype "passive"))
      (node (ref "C32") (pin "1") (pinfunction "1_1") (pintype "passive"))
      (node (ref "C33") (pin "1") (pinfunction "1_1") (pintype "passive"))
      (node (ref "C34") (pin "1") (pinfunction "1_1") (pintype "passive"))
      (node (ref "C36") (pin "1") (pinfunction "1_1") (pintype "passive"))
      (node (ref "C37") (pin "2") (pinfunction "2_2") (pintype "passive"))
      (node (ref "C38") (pin "1") (pinfunction "1_1") (pintype "passive"))
      (node (ref "C39") (pin "1") (pinfunction "1_1") (pintype "passive"))
      (node (ref "C4") (pin "2") (pinfunction "2_2") (pintype "passive"))
      (node (ref "C40") (pin "1") (pinfunction "1_1") (pintype "passive"))
      (node (ref "C5") (pin "1") (pinfunction "1_1") (pintype "passive"))
      (node (ref "C6") (pin "1") (pinfunction "1_1") (pintype "passive"))
      (node (ref "C7") (pin "1") (pinfunction "1_1") (pintype "passive"))
      (node (ref "C8") (pin "1") (pinfunction "1_1") (pintype "passive"))
      (node (ref "C9") (pin "1") (pinfunction "1_1") (pintype "passive"))
      (node (ref "J1") (pin "5") (pinfunction "5_5") (pintype "passive"))
      (node (ref "L5") (pin "2") (pinfunction "2_2") (pintype "passive"))
      (node (ref "L6") (pin "1") (pinfunction "1_1") (pintype "passive"))
      (node (ref "Q1") (pin "3") (pinfunction "DRAIN_3") (pintype "passive"))
      (node (ref "Q2") (pin "1") (pinfunction "Emitter_1") (pintype "passive"))
      (node (ref "R9") (pin "2") (pinfunction "2_2") (pintype "passive"))
      (node (ref "U1") (pin "15") (pinfunction "PB3_(PCINT3/OC2A/MOSI)_15") (pintype "bidirectional"))
      (node (ref "U1") (pin "21") (pinfunction "GND_21") (pintype "power_in"))
      (node (ref "U1") (pin "22") (pinfunction "ADC7_22") (pintype "input"))
      (node (ref "U1") (pin "23") (pinfunction "PC0_(ADC0/PCINT8)_23") (pintype "bidirectional"))
      (node (ref "U1") (pin "26") (pinfunction "PC3_(ADC3/PCINT11)_26") (pintype "bidirectional"))
      (node (ref "U2") (pin "2") (pinfunction "GND_2") (pintype "power_in"))
      (node (ref "U3") (pin "1") (pinfunction "Ground_1") (pintype "power_in"))
      (node (ref "U5") (pin "29") (pinfunction "GND_29") (pintype "power_in"))
      (node (ref "U5") (pin "3") (pinfunction "GND_3") (pintype "power_in"))
      (node (ref "X1") (pin "2") (pinfunction "GND_2") (pintype "power_in"))
      (node (ref "X1") (pin "4") (pinfunction "GND_4") (pintype "power_in"))
      (node (ref "X2") (pin "2") (pinfunction "GND_2") (pintype "power_in"))
      (node (ref "X2") (pin "4") (pinfunction "GND_4") (pintype "power_in"))
    )
    (net (code "23") (name "Net-(C2-Pad2)") (class "Default")
      (node (ref "C2") (pin "2") (pinfunction "2_2") (pintype "passive"))
      (node (ref "C8") (pin "2") (pinfunction "2_2") (pintype "passive"))
      (node (ref "L1") (pin "2") (pinfunction "2_2") (pintype "passive"))
      (node (ref "L2") (pin "1") (pinfunction "1_1") (pintype "passive"))
    )
    (net (code "24") (name "Net-(C3-Pad2)") (class "Default")
      (node (ref "C3") (pin "2") (pinfunction "2_2") (pintype "passive"))
      (node (ref "U1") (pin "4") (pinfunction "VCC_4") (pintype "power_in"))
    )
    (net (code "25") (name "Net-(C10-Pad2)") (class "Default")
      (node (ref "C10") (pin "2") (pinfunction "2_2") (pintype "passive"))
      (node (ref "C14") (pin "1") (pinfunction "1_1") (pintype "passive"))
    )
    (net (code "26") (name "Net-(C12-Pad2)") (class "Default")
      (node (ref "C12") (pin "2") (pinfunction "2_2") (pintype "passive"))
      (node (ref "L4") (pin "2") (pinfunction "2_2") (pintype "passive"))
    )
    (net (code "27") (name "Net-(C28-Pad2)") (class "Default")
      (node (ref "C28") (pin "2") (pinfunction "2_2") (pintype "passive"))
      (node (ref "C29") (pin "2") (pinfunction "2_2") (pintype "passive"))
    )
    (net (code "28") (name "Net-(C35-Pad2)") (class "Default")
      (node (ref "C35") (pin "2") (pinfunction "2_2") (pintype "passive"))
      (node (ref "C36") (pin "2") (pinfunction "2_2") (pintype "passive"))
    )
    (net (code "29") (name "Net-(DS1-A)") (class "Default")
      (node (ref "DS1") (pin "1") (pinfunction "A_1") (pintype "passive"))
      (node (ref "U4") (pin "14") (pinfunction "GPIO25_14") (pintype "bidirectional"))
    )
    (net (code "30") (name "Net-(DS1-K)") (class "Default")
      (node (ref "DS1") (pin "2") (pinfunction "K_2") (pintype "passive"))
      (node (ref "R9") (pin "1") (pinfunction "1_1") (pintype "passive"))
    )
    (net (code "31") (name "Net-(F1-Pad1)") (class "Default")
      (node (ref "F1") (pin "1") (pinfunction "1_1") (pintype "passive"))
      (node (ref "J1") (pin "1") (pinfunction "1_1") (pintype "passive"))
    )
    (net (code "32") (name "Net-(J1-Pad2)") (class "Default")
      (node (ref "J1") (pin "2") (pinfunction "2_2") (pintype "passive"))
      (node (ref "R6") (pin "1") (pinfunction "1_1") (pintype "passive"))
    )
    (net (code "33") (name "Net-(J1-Pad3)") (class "Default")
      (node (ref "J1") (pin "3") (pinfunction "3_3") (pintype "passive"))
      (node (ref "R7") (pin "1") (pinfunction "1_1") (pintype "passive"))
    )
    (net (code "34") (name "Net-(Q1-GATE)") (class "Default")
      (node (ref "Q1") (pin "1") (pinfunction "GATE_1") (pintype "passive"))
      (node (ref "Q3") (pin "1") (pinfunction "GATE_1") (pintype "passive"))
      (node (ref "R5") (pin "1") (pinfunction "1_1") (pintype "passive"))
    )
    (net (code "35") (name "Net-(Q1-SOURCE)") (class "Default")
      (node (ref "Q1") (pin "2") (pinfunction "SOURCE_2") (pintype "passive"))
      (node (ref "R2") (pin "1") (pinfunction "1_1") (pintype "passive"))
    )
    (net (code "36") (name "Net-(Q2-Base)") (class "Default")
      (node (ref "Q2") (pin "2") (pinfunction "Base_2") (pintype "passive"))
      (node (ref "R4") (pin "1") (pinfunction "1_1") (pintype "passive"))
    )
    (net (code "37") (name "Net-(Q2-Collector)") (class "Default")
      (node (ref "Q2") (pin "3") (pinfunction "Collector_3") (pintype "passive"))
      (node (ref "U2") (pin "4") (pinfunction "CTRL_4") (pintype "input"))
    )
    (net (code "38") (name "Net-(U1-PC2_(ADC2{slash}PCINT10))") (class "Default")
      (node (ref "C5") (pin "2") (pinfunction "2_2") (pintype "passive"))
      (node (ref "C6") (pin "2") (pinfunction "2_2") (pintype "passive"))
      (node (ref "L3") (pin "1") (pinfunction "1_1") (pintype "passive"))
      (node (ref "U1") (pin "25") (pinfunction "PC2_(ADC2/PCINT10)_25") (pintype "bidirectional"))
    )
    (net (code "39") (name "Net-(U1-PC4_(ADC4{slash}SDA{slash}PCINT12))") (class "Default")
      (node (ref "R3") (pin "2") (pinfunction "2_2") (pintype "passive"))
      (node (ref "U1") (pin "27") (pinfunction "PC4_(ADC4/SDA/PCINT12)_27") (pintype "bidirectional"))
    )
    (net (code "40") (name "Net-(U1-PC5_(ADC5{slash}SCL{slash}PCINT13))") (class "Default")
      (node (ref "C9") (pin "2") (pinfunction "2_2") (pintype "passive"))
      (node (ref "L1") (pin "1") (pinfunction "1_1") (pintype "passive"))
      (node (ref "L3") (pin "2") (pinfunction "2_2") (pintype "passive"))
      (node (ref "R3") (pin "1") (pinfunction "1_1") (pintype "passive"))
      (node (ref "U1") (pin "28") (pinfunction "PC5_(ADC5/SCL/PCINT13)_28") (pintype "bidirectional"))
    )
    (net (code "41") (name "Net-(U1-PD3_(PCINT19{slash}OC2B{slash}INT1))") (class "Default")
      (node (ref "C14") (pin "2") (pinfunction "2_2") (pintype "passive"))
      (node (ref "L5") (pin "1") (pinfunction "1_1") (pintype "passive"))
      (node (ref "U1") (pin "1") (pinfunction "PD3_(PCINT19/OC2B/INT1)_1") (pintype "bidirectional"))
    )
    (net (code "42") (name "Net-(U1-PD4_(PCINT20{slash}XCK{slash}T0))") (class "Default")
      (node (ref "C13") (pin "1") (pinfunction "1_1") (pintype "passive"))
      (node (ref "U1") (pin "2") (pinfunction "PD4_(PCINT20/XCK/T0)_2") (pintype "bidirectional"))
    )
    (net (code "43") (name "Net-(U2-RF1)") (class "Default")
      (node (ref "C10") (pin "1") (pinfunction "1_1") (pintype "passive"))
      (node (ref "U2") (pin "1") (pinfunction "RF1_1") (pintype "passive"))
    )
    (net (code "44") (name "Net-(U2-RF2)") (class "Default")
      (node (ref "C2") (pin "1") (pinfunction "1_1") (pintype "passive"))
      (node (ref "C7") (pin "2") (pinfunction "2_2") (pintype "passive"))
      (node (ref "L2") (pin "2") (pinfunction "2_2") (pintype "passive"))
      (node (ref "U2") (pin "3") (pinfunction "RF2_3") (pintype "passive"))
    )
    (net (code "45") (name "Net-(U2-RFC)") (class "Default")
      (node (ref "C11") (pin "2") (pinfunction "2_2") (pintype "passive"))
      (node (ref "L4") (pin "1") (pinfunction "1_1") (pintype "passive"))
      (node (ref "U2") (pin "5") (pinfunction "RFC_5") (pintype "passive"))
    )
    (net (code "46") (name "Net-(U3-VIN)") (class "Default")
      (node (ref "C23") (pin "1") (pinfunction "1_1") (pintype "passive"))
      (node (ref "F1") (pin "2") (pinfunction "2_2") (pintype "passive"))
      (node (ref "U3") (pin "3") (pinfunction "VIN_3") (pintype "power_in"))
    )
    (net (code "47") (name "Net-(U4-32K_XN)") (class "Default")
      (node (ref "C40") (pin "2") (pinfunction "2_2") (pintype "passive"))
      (node (ref "U4") (pin "13") (pinfunction "32K_XN_13") (pintype "bidirectional"))
      (node (ref "Y1") (pin "2") (pinfunction "2_2") (pintype "passive"))
    )
    (net (code "48") (name "Net-(U4-32K_XP)") (class "Default")
      (node (ref "C39") (pin "2") (pinfunction "2_2") (pintype "passive"))
      (node (ref "U4") (pin "12") (pinfunction "32K_XP_12") (pintype "bidirectional"))
      (node (ref "Y1") (pin "1") (pinfunction "1_1") (pintype "passive"))
    )
    (net (code "49") (name "Net-(U4-CAP1)") (class "Default")
      (node (ref "C38") (pin "2") (pinfunction "2_2") (pintype "passive"))
      (node (ref "C41") (pin "1") (pinfunction "1_1") (pintype "passive"))
      (node (ref "R11") (pin "1") (pinfunction "1_1") (pintype "passive"))
      (node (ref "U4") (pin "48") (pinfunction "CAP1_48") (pintype "input"))
    )
    (net (code "50") (name "Net-(U4-CAP2)") (class "Default")
      (node (ref "C41") (pin "2") (pinfunction "2_2") (pintype "passive"))
      (node (ref "R11") (pin "2") (pinfunction "2_2") (pintype "passive"))
      (node (ref "U4") (pin "47") (pinfunction "CAP2_47") (pintype "input"))
    )
    (net (code "51") (name "Net-(U4-LNA_IN)") (class "Default")
      (node (ref "C35") (pin "1") (pinfunction "1_1") (pintype "passive"))
      (node (ref "L6") (pin "2") (pinfunction "2_2") (pintype "passive"))
      (node (ref "U4") (pin "2") (pinfunction "LNA_IN_2") (pintype "bidirectional"))
    )
    (net (code "52") (name "Net-(U4-SENSOR_CAPN)") (class "Default")
      (node (ref "C30") (pin "2") (pinfunction "2_2") (pintype "passive"))
      (node (ref "U4") (pin "7") (pinfunction "SENSOR_CAPN_7") (pintype "input"))
    )
    (net (code "53") (name "Net-(U4-SENSOR_CAPP)") (class "Default")
      (node (ref "C31") (pin "1") (pinfunction "1_1") (pintype "passive"))
      (node (ref "U4") (pin "6") (pinfunction "SENSOR_CAPP_6") (pintype "input"))
    )
    (net (code "54") (name "Net-(U4-SENSOR_VN)") (class "Default")
      (node (ref "C30") (pin "1") (pinfunction "1_1") (pintype "passive"))
      (node (ref "U4") (pin "8") (pinfunction "SENSOR_VN_8") (pintype "input"))
    )
    (net (code "55") (name "Net-(U4-SENSOR_VP)") (class "Default")
      (node (ref "C31") (pin "2") (pinfunction "2_2") (pintype "passive"))
      (node (ref "U4") (pin "5") (pinfunction "SENSOR_VP_5") (pintype "input"))
    )
    (net (code "56") (name "Net-(U4-U0RXD)") (class "Default")
      (node (ref "R10") (pin "2") (pinfunction "2_2") (pintype "passive"))
      (node (ref "U4") (pin "40") (pinfunction "U0RXD_40") (pintype "bidirectional"))
    )
    (net (code "57") (name "Net-(U4-XTAL_N)") (class "Default")
      (node (ref "C33") (pin "2") (pinfunction "2_2") (pintype "passive"))
      (node (ref "U4") (pin "44") (pinfunction "XTAL_N_44") (pintype "output"))
      (node (ref "X2") (pin "3") (pinfunction "X2_3") (pintype "passive"))
    )
    (net (code "58") (name "Net-(U4-XTAL_P)") (class "Default")
      (node (ref "C37") (pin "1") (pinfunction "1_1") (pintype "passive"))
      (node (ref "U4") (pin "45") (pinfunction "XTAL_P_45") (pintype "input"))
      (node (ref "X2") (pin "1") (pinfunction "X1_1") (pintype "passive"))
    )
    (net (code "59") (name "Net-(U5A-VDD)") (class "Default")
      (node (ref "C34") (pin "2") (pinfunction "2_2") (pintype "passive"))
      (node (ref "U5") (pin "6") (pinfunction "VDD_6") (pintype "power_in"))
    )
    (net (code "60") (name "Net-(U5A-~{RST})") (class "Default")
      (node (ref "R8") (pin "1") (pinfunction "1_1") (pintype "passive"))
      (node (ref "U5") (pin "9") (pinfunction "~{RST}_9") (pintype "bidirectional"))
    )
    (net (code "61") (name "Net-(X1-X1)") (class "Default")
      (node (ref "C15") (pin "1") (pinfunction "1_1") (pintype "passive"))
      (node (ref "U1") (pin "5") (pinfunction "GND_5") (pintype "power_in"))
      (node (ref "X1") (pin "1") (pinfunction "X1_1") (pintype "passive"))
    )
    (net (code "62") (name "Net-(X1-X2)") (class "Default")
      (node (ref "C4") (pin "1") (pinfunction "1_1") (pintype "passive"))
      (node (ref "U1") (pin "6") (pinfunction "VCC_6") (pintype "power_in"))
      (node (ref "X1") (pin "3") (pinfunction "X2_3") (pintype "passive"))
    )
    (net (code "63") (name "VBAT") (class "Default")
      (node (ref "R1") (pin "1") (pinfunction "1_1") (pintype "passive"))
    )
    (net (code "64") (name "Vext") (class "Default")
      (node (ref "C16") (pin "1") (pinfunction "1_1") (pintype "passive"))
      (node (ref "Q3") (pin "3") (pinfunction "DRAIN_3") (pintype "passive"))
      (node (ref "U2") (pin "6") (pinfunction "~{CTRL}/VDD_6") (pintype "input"))
    )
    (net (code "65") (name "unconnected-(J1-Pad4)") (class "Default")
      (node (ref "J1") (pin "4") (pinfunction "4_4") (pintype "passive+no_connect"))
    )
    (net (code "66") (name "unconnected-(U1-PB0_(PCINT0{slash}CLKO{slash}ICP1)-Pad12)") (class "Default")
      (node (ref "U1") (pin "12") (pinfunction "PB0_(PCINT0/CLKO/ICP1)_12") (pintype "bidirectional+no_connect"))
    )
    (net (code "67") (name "unconnected-(U1-PB1_(PCINT1{slash}OC1A)-Pad13)") (class "Default")
      (node (ref "U1") (pin "13") (pinfunction "PB1_(PCINT1/OC1A)_13") (pintype "bidirectional+no_connect"))
    )
    (net (code "68") (name "unconnected-(U1-PD7_(PCINT23{slash}AIN1)-Pad11)") (class "Default")
      (node (ref "U1") (pin "11") (pinfunction "PD7_(PCINT23/AIN1)_11") (pintype "bidirectional+no_connect"))
    )
    (net (code "69") (name "unconnected-(U3-VOUT-Pad4)") (class "Default")
      (node (ref "U3") (pin "4") (pinfunction "VOUT_4") (pintype "passive+no_connect"))
    )
    (net (code "70") (name "unconnected-(U4-CHIP_PU-Pad9)") (class "Default")
      (node (ref "U4") (pin "9") (pinfunction "CHIP_PU_9") (pintype "input"))
    )
    (net (code "71") (name "unconnected-(U4-GND-Pad49)") (class "Default")
      (node (ref "U4") (pin "49") (pinfunction "GND_49") (pintype "power_in"))
    )
    (net (code "72") (name "unconnected-(U4-GPIO0-Pad23)") (class "Default")
      (node (ref "U4") (pin "23") (pinfunction "GPIO0_23") (pintype "bidirectional"))
    )
    (net (code "73") (name "unconnected-(U4-GPIO2-Pad22)") (class "Default")
      (node (ref "U4") (pin "22") (pinfunction "GPIO2_22") (pintype "bidirectional"))
    )
    (net (code "74") (name "unconnected-(U4-GPIO4-Pad24)") (class "Default")
      (node (ref "U4") (pin "24") (pinfunction "GPIO4_24") (pintype "bidirectional"))
    )
    (net (code "75") (name "unconnected-(U4-GPIO5-Pad34)") (class "Default")
      (node (ref "U4") (pin "34") (pinfunction "GPIO5_34") (pintype "bidirectional"))
    )
    (net (code "76") (name "unconnected-(U4-GPIO16-Pad25)") (class "Default")
      (node (ref "U4") (pin "25") (pinfunction "GPIO16_25") (pintype "bidirectional"))
    )
    (net (code "77") (name "unconnected-(U4-GPIO17-Pad27)") (class "Default")
      (node (ref "U4") (pin "27") (pinfunction "GPIO17_27") (pintype "bidirectional"))
    )
    (net (code "78") (name "unconnected-(U4-GPIO18-Pad35)") (class "Default")
      (node (ref "U4") (pin "35") (pinfunction "GPIO18_35") (pintype "bidirectional"))
    )
    (net (code "79") (name "unconnected-(U4-GPIO19-Pad38)") (class "Default")
      (node (ref "U4") (pin "38") (pinfunction "GPIO19_38") (pintype "bidirectional"))
    )
    (net (code "80") (name "unconnected-(U4-GPIO22-Pad39)") (class "Default")
      (node (ref "U4") (pin "39") (pinfunction "GPIO22_39") (pintype "bidirectional"))
    )
    (net (code "81") (name "unconnected-(U4-GPIO23-Pad36)") (class "Default")
      (node (ref "U4") (pin "36") (pinfunction "GPIO23_36") (pintype "bidirectional"))
    )
    (net (code "82") (name "unconnected-(U4-GPIO26-Pad15)") (class "Default")
      (node (ref "U4") (pin "15") (pinfunction "GPIO26_15") (pintype "bidirectional"))
    )
    (net (code "83") (name "unconnected-(U4-GPIO27-Pad16)") (class "Default")
      (node (ref "U4") (pin "16") (pinfunction "GPIO27_16") (pintype "bidirectional"))
    )
    (net (code "84") (name "unconnected-(U4-MTDI-Pad18)") (class "Default")
      (node (ref "U4") (pin "18") (pinfunction "MTDI_18") (pintype "bidirectional"))
    )
    (net (code "85") (name "unconnected-(U4-MTDO-Pad21)") (class "Default")
      (node (ref "U4") (pin "21") (pinfunction "MTDO_21") (pintype "bidirectional"))
    )
    (net (code "86") (name "unconnected-(U4-MTMS-Pad17)") (class "Default")
      (node (ref "U4") (pin "17") (pinfunction "MTMS_17") (pintype "bidirectional"))
    )
    (net (code "87") (name "unconnected-(U4-SD_CLK-Pad31)") (class "Default")
      (node (ref "U4") (pin "31") (pinfunction "SD_CLK_31") (pintype "bidirectional"))
    )
    (net (code "88") (name "unconnected-(U4-SD_CMD-Pad30)") (class "Default")
      (node (ref "U4") (pin "30") (pinfunction "SD_CMD_30") (pintype "bidirectional"))
    )
    (net (code "89") (name "unconnected-(U4-SD_DATA_0-Pad32)") (class "Default")
      (node (ref "U4") (pin "32") (pinfunction "SD_DATA_0_32") (pintype "bidirectional"))
    )
    (net (code "90") (name "unconnected-(U4-SD_DATA_1-Pad33)") (class "Default")
      (node (ref "U4") (pin "33") (pinfunction "SD_DATA_1_33") (pintype "bidirectional"))
    )
    (net (code "91") (name "unconnected-(U4-SD_DATA_2-Pad28)") (class "Default")
      (node (ref "U4") (pin "28") (pinfunction "SD_DATA_2_28") (pintype "bidirectional"))
    )
    (net (code "92") (name "unconnected-(U4-SD_DATA_3-Pad29)") (class "Default")
      (node (ref "U4") (pin "29") (pinfunction "SD_DATA_3_29") (pintype "bidirectional"))
    )
    (net (code "93") (name "unconnected-(U4-U0TXD-Pad41)") (class "Default")
      (node (ref "U4") (pin "41") (pinfunction "U0TXD_41") (pintype "bidirectional"))
    )
    (net (code "94") (name "unconnected-(U4-VDD_SDIO-Pad26)") (class "Default")
      (node (ref "U4") (pin "26") (pinfunction "VDD_SDIO_26") (pintype "power_in"))
    )
    (net (code "95") (name "unconnected-(U5A-SUSPEND-Pad12)") (class "Default")
      (node (ref "U5") (pin "12") (pinfunction "SUSPEND_12") (pintype "output+no_connect"))
    )
    (net (code "96") (name "unconnected-(U5A-~{CTS}-Pad23)") (class "Default")
      (node (ref "U5") (pin "23") (pinfunction "~{CTS}_23") (pintype "input+no_connect"))
    )
    (net (code "97") (name "unconnected-(U5A-~{DCD}-Pad1)") (class "Default")
      (node (ref "U5") (pin "1") (pinfunction "~{DCD}_1") (pintype "input+no_connect"))
    )
    (net (code "98") (name "unconnected-(U5A-~{DSR}-Pad27)") (class "Default")
      (node (ref "U5") (pin "27") (pinfunction "~{DSR}_27") (pintype "input+no_connect"))
    )
    (net (code "99") (name "unconnected-(U5A-~{RI}-Pad2)") (class "Default")
      (node (ref "U5") (pin "2") (pinfunction "~{RI}_2") (pintype "input+no_connect"))
    )
    (net (code "100") (name "unconnected-(U5A-~{SUSPEND}-Pad11)") (class "Default")
      (node (ref "U5") (pin "11") (pinfunction "~{SUSPEND}_11") (pintype "output+no_connect"))
    )
  )
)
